# CAN.net
KiCad netlist of a schematic drawn in Altium Designer
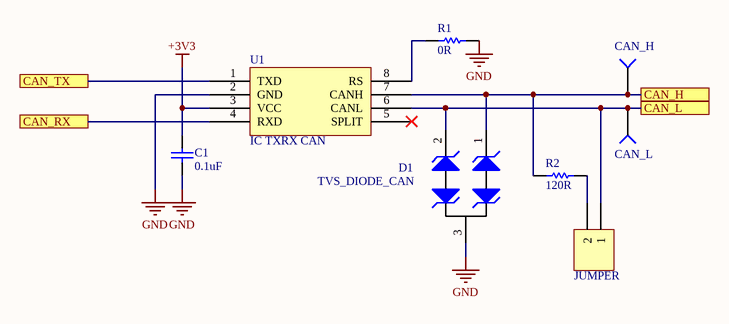
[diagram p0: CAN.SchDoc]

(export (version "E")
  (design (tool "Eeschema 10.0.6"))
  (components
    (comp (ref "1")
      (value "JUMPER")
      (footprint "HDR1X2")
      (description "Header, 2-Pin")
      (fields (field (name "PUBLISHER") "Altium Limited"))
      (libsource (lib "Miscellaneous Connectors") (part "Header 2"))
    )
    (comp (ref "C1")
      (value "0.1uF")
      (footprint "CAPC0603(1608)55_N")
      (description "CAP CER 0.1UF 16V X7R 0603")
      (fields (field (name "PART NUMBER") "CC0603KRX7R7BB104") (field (name "MANUFACTURER") "Yageo"))
      (libsource (lib "UWRT_Schematic_Library_2019") (part "CAP_0.1uF_16V_0603"))
    )
    (comp (ref "D1")
      (value "TVS_DIODE_CAN")
      (footprint "UWRT_Footprint_Library_2019:TVS_DIODE_CAN")
      (description "TVS DIODE 24V 41V SOT323-3")
      (fields (field (name "PART NUMBER") "PESD2CAN,215") (field (name "MANUFACTURER") "Nexperia USA Inc."))
      (libsource (lib "UWRT_Schematic_Library_2019") (part "TVS_DIODE_CAN"))
    )
    (comp (ref "R1")
      (value "0R")
      (footprint "RESC0603(1608)_N")
      (description "RES SMD 0 OHM JUMPER 1/10W 0603")
      (fields (field (name "MANUFACTURER") "Yageo") (field (name "Comment") "RES_0R_0603"))
      (libsource (lib "UWRT_Schematic_Library_2019") (part "RES_0R_0603"))
    )
    (comp (ref "R2")
      (value "120R")
      (footprint "RESC0603(1608)_N")
      (description "RES SMD 120 OHM 5% 1/10W 0603")
      (fields (field (name "MANUFACTURER") "Yageo") (field (name "TOLERANCE") "5%"))
      (libsource (lib "UWRT_Schematic_Library_2019") (part "RES_120R_0603"))
    )
    (comp (ref "TP1")
      (value "CAN_H")
      (footprint "TESTPOINT")
      (libsource (lib "UWRT_Schematic_Library_2019") (part "TESTPOINT_SMD"))
    )
    (comp (ref "TP2")
      (value "CAN_L")
      (footprint "TESTPOINT")
      (libsource (lib "UWRT_Schematic_Library_2019") (part "TESTPOINT_SMD"))
    )
    (comp (ref "U1")
      (value "IC TXRX CAN")
      (footprint "LTC2875")
      (description "IC TXRX CAN 4MBPS 8SO")
      (fields
        (field (name "MANUFACTURER") "Linear Technologies")
        (field (name "PART NUMBER") "LTC2875IS8#PBF")
      )
      (libsource (lib "UWRT_Schematic_Library_2019") (part "LTC2875"))
    )
  )
  (nets
    (net (code "1") (name "+3V3") (class "Default")
      (node (ref "C1") (pin "2") (pinfunction "2_2") (pintype "passive"))
      (node (ref "U1") (pin "3") (pinfunction "VCC_3") (pintype "passive"))
    )
    (net (code "2") (name "/CAN_H") (class "Default")
      (node (ref "D1") (pin "1") (pinfunction "1_1") (pintype "passive"))
      (node (ref "R2") (pin "1") (pinfunction "1_1") (pintype "passive"))
      (node (ref "TP1") (pin "1") (pinfunction "=value_1") (pintype "passive"))
      (node (ref "U1") (pin "7") (pinfunction "CANH_7") (pintype "passive"))
    )
    (net (code "3") (name "/CAN_L") (class "Default")
      (node (ref "1") (pin "1") (pinfunction "1_1") (pintype "passive"))
      (node (ref "D1") (pin "2") (pinfunction "2_2") (pintype "passive"))
      (node (ref "TP2") (pin "1") (pinfunction "=value_1") (pintype "passive"))
      (node (ref "U1") (pin "6") (pinfunction "CANL_6") (pintype "passive"))
    )
    (net (code "4") (name "/CAN_RX") (class "Default")
      (node (ref "U1") (pin "4") (pinfunction "RXD_4") (pintype "passive"))
    )
    (net (code "5") (name "/CAN_TX") (class "Default")
      (node (ref "U1") (pin "1") (pinfunction "TXD_1") (pintype "passive"))
    )
    (net (code "6") (name "GND") (class "Default")
      (node (ref "C1") (pin "1") (pinfunction "1_1") (pintype "passive"))
      (node (ref "D1") (pin "3") (pinfunction "3_3") (pintype "passive"))
      (node (ref "R1") (pin "2") (pinfunction "2_2") (pintype "passive"))
      (node (ref "U1") (pin "2") (pinfunction "GND_2") (pintype "passive"))
    )
    (net (code "7") (name "Net-(1-Pad2)") (class "Default")
      (node (ref "1") (pin "2") (pinfunction "2_2") (pintype "passive"))
      (node (ref "R2") (pin "2") (pinfunction "2_2") (pintype "passive"))
    )
    (net (code "8") (name "Net-(U1-RS)") (class "Default")
      (node (ref "R1") (pin "1") (pinfunction "1_1") (pintype "passive"))
      (node (ref "U1") (pin "8") (pinfunction "RS_8") (pintype "passive"))
    )
    (net (code "9") (name "unconnected-(U1-SPLIT-Pad5)") (class "Default")
      (node (ref "U1") (pin "5") (pinfunction "SPLIT_5") (pintype "passive+no_connect"))
    )
  )
)
